# LN2_Autofill_Connectors.net
KiCad netlist of a schematic drawn in EAGLE
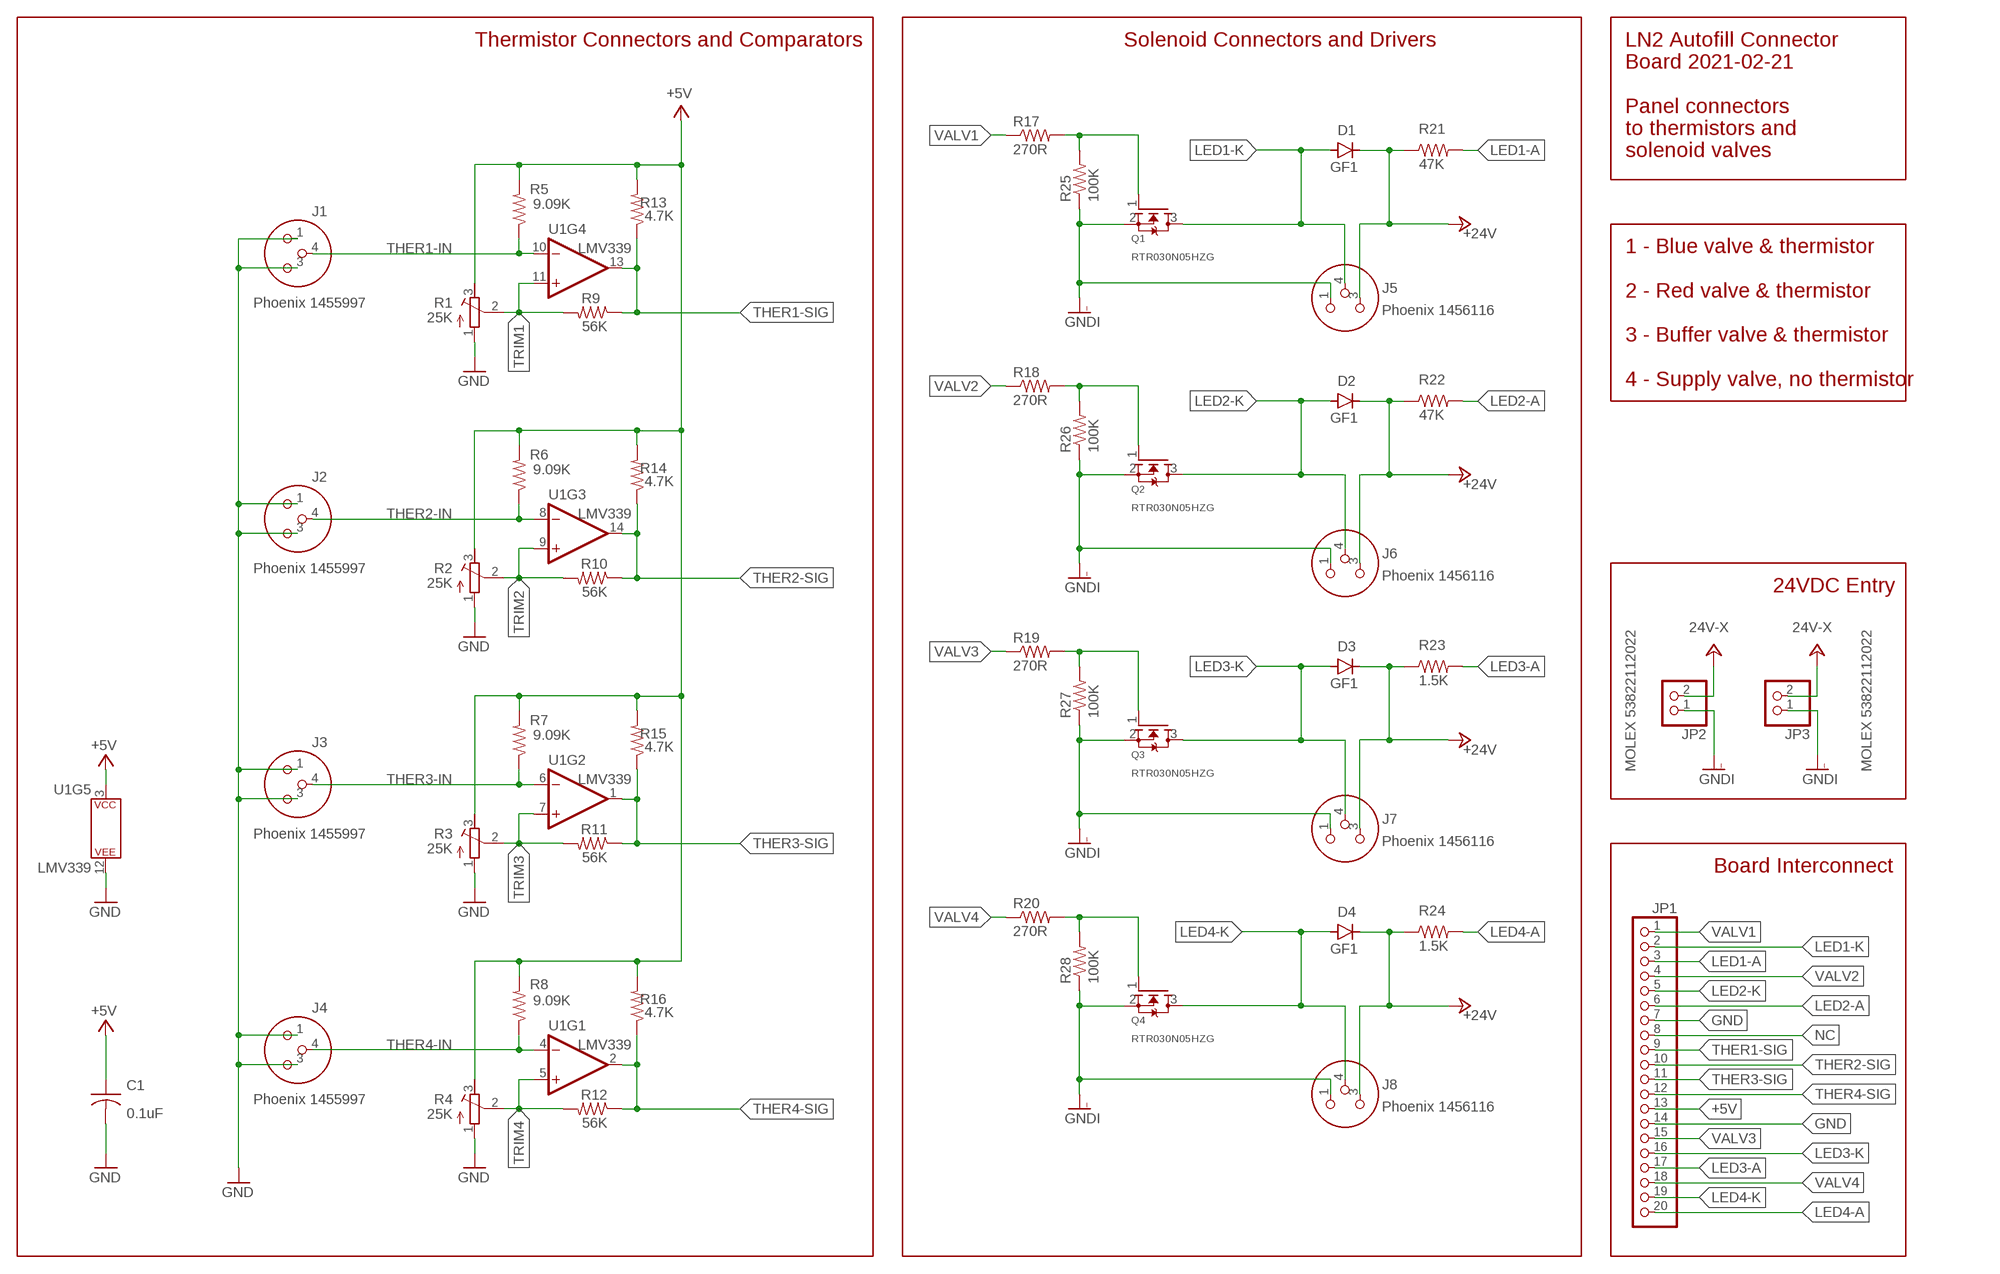
[diagram p0: schematic, sheet 1]

(export (version "E")
  (design (tool "Eeschema 10.0.6"))
  (components
    (comp (ref "C1")
      (value "0.1uF")
      (footprint "eagle-import:C0805")
      (libsource (lib "eagle-import") (part "C-USC0805"))
    )
    (comp (ref "D1")
      (value "GF1")
      (footprint "eagle-import:SMA-DO214AC")
      (libsource (lib "eagle-import") (part "GF1"))
    )
    (comp (ref "D2")
      (value "GF1")
      (footprint "eagle-import:SMA-DO214AC")
      (libsource (lib "eagle-import") (part "GF1"))
    )
    (comp (ref "D3")
      (value "GF1")
      (footprint "eagle-import:SMA-DO214AC")
      (libsource (lib "eagle-import") (part "GF1"))
    )
    (comp (ref "D4")
      (value "GF1")
      (footprint "eagle-import:SMA-DO214AC")
      (libsource (lib "eagle-import") (part "GF1"))
    )
    (comp (ref "J1")
      (value "Phoenix 1455997")
      (footprint "eagle-import:PHOENIX-3PIN")
      (libsource (lib "eagle-import") (part "PHOENIX-3PIN-MALE"))
    )
    (comp (ref "J2")
      (value "Phoenix 1455997")
      (footprint "eagle-import:PHOENIX-3PIN")
      (libsource (lib "eagle-import") (part "PHOENIX-3PIN-MALE"))
    )
    (comp (ref "J3")
      (value "Phoenix 1455997")
      (footprint "eagle-import:PHOENIX-3PIN")
      (libsource (lib "eagle-import") (part "PHOENIX-3PIN-MALE"))
    )
    (comp (ref "J4")
      (value "Phoenix 1455997")
      (footprint "eagle-import:PHOENIX-3PIN")
      (libsource (lib "eagle-import") (part "PHOENIX-3PIN-MALE"))
    )
    (comp (ref "J5")
      (value "Phoenix 1456116")
      (footprint "eagle-import:PHOENIX-3PIN-FEMALE")
      (libsource (lib "eagle-import") (part "PHOENIX-3PIN-FEMALE"))
    )
    (comp (ref "J6")
      (value "Phoenix 1456116")
      (footprint "eagle-import:PHOENIX-3PIN-FEMALE")
      (libsource (lib "eagle-import") (part "PHOENIX-3PIN-FEMALE"))
    )
    (comp (ref "J7")
      (value "Phoenix 1456116")
      (footprint "eagle-import:PHOENIX-3PIN-FEMALE")
      (libsource (lib "eagle-import") (part "PHOENIX-3PIN-FEMALE"))
    )
    (comp (ref "J8")
      (value "Phoenix 1456116")
      (footprint "eagle-import:PHOENIX-3PIN-FEMALE")
      (libsource (lib "eagle-import") (part "PHOENIX-3PIN-FEMALE"))
    )
    (comp (ref "JP1")
      (value "PINHD-1X20")
      (footprint "eagle-import:1X20")
      (libsource (lib "eagle-import") (part "PINHD-1X20"))
    )
    (comp (ref "JP2")
      (value "MOLEX 53822112022")
      (footprint "eagle-import:MOLEX-02-VERT")
      (libsource (lib "eagle-import") (part "PINHD-1X2MOLEX-02-VERT"))
    )
    (comp (ref "JP3")
      (value "MOLEX 53822112022")
      (footprint "eagle-import:MOLEX-02-VERT")
      (libsource (lib "eagle-import") (part "PINHD-1X2MOLEX-02-VERT"))
    )
    (comp (ref "Q1")
      (value "RTR030N05HZG")
      (footprint "eagle-import:SOT23")
      (libsource (lib "eagle-import") (part "MOSFET-NREFLOW"))
    )
    (comp (ref "Q2")
      (value "RTR030N05HZG")
      (footprint "eagle-import:SOT23")
      (libsource (lib "eagle-import") (part "MOSFET-NREFLOW"))
    )
    (comp (ref "Q3")
      (value "RTR030N05HZG")
      (footprint "eagle-import:SOT23")
      (libsource (lib "eagle-import") (part "MOSFET-NREFLOW"))
    )
    (comp (ref "Q4")
      (value "RTR030N05HZG")
      (footprint "eagle-import:SOT23")
      (libsource (lib "eagle-import") (part "MOSFET-NREFLOW"))
    )
    (comp (ref "R1")
      (value "25K")
      (footprint "eagle-import:RTRIM3296Y")
      (libsource (lib "eagle-import") (part "R-TRIMM3296Y"))
    )
    (comp (ref "R2")
      (value "25K")
      (footprint "eagle-import:RTRIM3296Y")
      (libsource (lib "eagle-import") (part "R-TRIMM3296Y"))
    )
    (comp (ref "R3")
      (value "25K")
      (footprint "eagle-import:RTRIM3296Y")
      (libsource (lib "eagle-import") (part "R-TRIMM3296Y"))
    )
    (comp (ref "R4")
      (value "25K")
      (footprint "eagle-import:RTRIM3296Y")
      (libsource (lib "eagle-import") (part "R-TRIMM3296Y"))
    )
    (comp (ref "R5")
      (value "9.09K")
      (footprint "eagle-import:R0805")
      (libsource (lib "eagle-import") (part "R-US_R0805"))
    )
    (comp (ref "R6")
      (value "9.09K")
      (footprint "eagle-import:R0805")
      (libsource (lib "eagle-import") (part "R-US_R0805"))
    )
    (comp (ref "R7")
      (value "9.09K")
      (footprint "eagle-import:R0805")
      (libsource (lib "eagle-import") (part "R-US_R0805"))
    )
    (comp (ref "R8")
      (value "9.09K")
      (footprint "eagle-import:R0805")
      (libsource (lib "eagle-import") (part "R-US_R0805"))
    )
    (comp (ref "R9")
      (value "56K")
      (footprint "eagle-import:R0805")
      (libsource (lib "eagle-import") (part "R-US_R0805"))
    )
    (comp (ref "R10")
      (value "56K")
      (footprint "eagle-import:R0805")
      (libsource (lib "eagle-import") (part "R-US_R0805"))
    )
    (comp (ref "R11")
      (value "56K")
      (footprint "eagle-import:R0805")
      (libsource (lib "eagle-import") (part "R-US_R0805"))
    )
    (comp (ref "R12")
      (value "56K")
      (footprint "eagle-import:R0805")
      (libsource (lib "eagle-import") (part "R-US_R0805"))
    )
    (comp (ref "R13")
      (value "4.7K")
      (footprint "eagle-import:R0805")
      (libsource (lib "eagle-import") (part "R-US_R0805"))
    )
    (comp (ref "R14")
      (value "4.7K")
      (footprint "eagle-import:R0805")
      (libsource (lib "eagle-import") (part "R-US_R0805"))
    )
    (comp (ref "R15")
      (value "4.7K")
      (footprint "eagle-import:R0805")
      (libsource (lib "eagle-import") (part "R-US_R0805"))
    )
    (comp (ref "R16")
      (value "4.7K")
      (footprint "eagle-import:R0805")
      (libsource (lib "eagle-import") (part "R-US_R0805"))
    )
    (comp (ref "R17")
      (value "270R")
      (footprint "eagle-import:R0805")
      (libsource (lib "eagle-import") (part "R-US_R0805"))
    )
    (comp (ref "R18")
      (value "270R")
      (footprint "eagle-import:R0805")
      (libsource (lib "eagle-import") (part "R-US_R0805"))
    )
    (comp (ref "R19")
      (value "270R")
      (footprint "eagle-import:R0805")
      (libsource (lib "eagle-import") (part "R-US_R0805"))
    )
    (comp (ref "R20")
      (value "270R")
      (footprint "eagle-import:R0805")
      (libsource (lib "eagle-import") (part "R-US_R0805"))
    )
    (comp (ref "R21")
      (value "47K")
      (footprint "eagle-import:R0805")
      (libsource (lib "eagle-import") (part "R-US_R0805"))
    )
    (comp (ref "R22")
      (value "47K")
      (footprint "eagle-import:R0805")
      (libsource (lib "eagle-import") (part "R-US_R0805"))
    )
    (comp (ref "R23")
      (value "1.5K")
      (footprint "eagle-import:R0805")
      (libsource (lib "eagle-import") (part "R-US_R0805"))
    )
    (comp (ref "R24")
      (value "1.5K")
      (footprint "eagle-import:R0805")
      (libsource (lib "eagle-import") (part "R-US_R0805"))
    )
    (comp (ref "R25")
      (value "100K")
      (footprint "eagle-import:R0805")
      (libsource (lib "eagle-import") (part "R-US_R0805"))
    )
    (comp (ref "R26")
      (value "100K")
      (footprint "eagle-import:R0805")
      (libsource (lib "eagle-import") (part "R-US_R0805"))
    )
    (comp (ref "R27")
      (value "100K")
      (footprint "eagle-import:R0805")
      (libsource (lib "eagle-import") (part "R-US_R0805"))
    )
    (comp (ref "R28")
      (value "100K")
      (footprint "eagle-import:R0805")
      (libsource (lib "eagle-import") (part "R-US_R0805"))
    )
    (comp (ref "U1")
      (value "LMV339")
      (footprint "eagle-import:SOIC127P599X175-14")
      (libsource (lib "eagle-import") (part "LM339SOIC-14"))
    )
  )
  (nets
    (net (code "1") (name "+5V") (class "Default")
      (node (ref "C1") (pin "1") (pinfunction "1_1") (pintype "passive"))
      (node (ref "JP1") (pin "13") (pinfunction "13_13") (pintype "passive"))
      (node (ref "R1") (pin "3") (pinfunction "E_3") (pintype "passive"))
      (node (ref "R13") (pin "2") (pinfunction "2_2") (pintype "passive"))
      (node (ref "R14") (pin "2") (pinfunction "2_2") (pintype "passive"))
      (node (ref "R15") (pin "2") (pinfunction "2_2") (pintype "passive"))
      (node (ref "R16") (pin "2") (pinfunction "2_2") (pintype "passive"))
      (node (ref "R2") (pin "3") (pinfunction "E_3") (pintype "passive"))
      (node (ref "R3") (pin "3") (pinfunction "E_3") (pintype "passive"))
      (node (ref "R4") (pin "3") (pinfunction "E_3") (pintype "passive"))
      (node (ref "R5") (pin "2") (pinfunction "2_2") (pintype "passive"))
      (node (ref "R6") (pin "2") (pinfunction "2_2") (pintype "passive"))
      (node (ref "R7") (pin "2") (pinfunction "2_2") (pintype "passive"))
      (node (ref "R8") (pin "2") (pinfunction "2_2") (pintype "passive"))
      (node (ref "U1") (pin "3") (pinfunction "P$V+_3") (pintype "bidirectional"))
    )
    (net (code "2") (name "+24V") (class "Default")
      (node (ref "D1") (pin "K") (pinfunction "C_K") (pintype "passive"))
      (node (ref "D2") (pin "K") (pinfunction "C_K") (pintype "passive"))
      (node (ref "D3") (pin "K") (pinfunction "C_K") (pintype "passive"))
      (node (ref "D4") (pin "K") (pinfunction "C_K") (pintype "passive"))
      (node (ref "J5") (pin "3") (pinfunction "3_3") (pintype "passive"))
      (node (ref "J6") (pin "3") (pinfunction "3_3") (pintype "passive"))
      (node (ref "J7") (pin "3") (pinfunction "3_3") (pintype "passive"))
      (node (ref "J8") (pin "3") (pinfunction "3_3") (pintype "passive"))
      (node (ref "JP2") (pin "2") (pinfunction "2_2") (pintype "passive"))
      (node (ref "JP3") (pin "2") (pinfunction "2_2") (pintype "passive"))
      (node (ref "R21") (pin "1") (pinfunction "1_1") (pintype "passive"))
      (node (ref "R22") (pin "1") (pinfunction "1_1") (pintype "passive"))
      (node (ref "R23") (pin "1") (pinfunction "1_1") (pintype "passive"))
      (node (ref "R24") (pin "1") (pinfunction "1_1") (pintype "passive"))
    )
    (net (code "3") (name "/THER1-IN") (class "Default")
      (node (ref "J1") (pin "4") (pinfunction "4_4") (pintype "passive"))
      (node (ref "R5") (pin "1") (pinfunction "1_1") (pintype "passive"))
      (node (ref "U1") (pin "10") (pinfunction "-IN_10") (pintype "input"))
    )
    (net (code "4") (name "/THER2-IN") (class "Default")
      (node (ref "J2") (pin "4") (pinfunction "4_4") (pintype "passive"))
      (node (ref "R6") (pin "1") (pinfunction "1_1") (pintype "passive"))
      (node (ref "U1") (pin "8") (pinfunction "-IN_8") (pintype "input"))
    )
    (net (code "5") (name "/THER3-IN") (class "Default")
      (node (ref "J3") (pin "4") (pinfunction "4_4") (pintype "passive"))
      (node (ref "R7") (pin "1") (pinfunction "1_1") (pintype "passive"))
      (node (ref "U1") (pin "6") (pinfunction "-IN_6") (pintype "input"))
    )
    (net (code "6") (name "/THER4-IN") (class "Default")
      (node (ref "J4") (pin "4") (pinfunction "4_4") (pintype "passive"))
      (node (ref "R8") (pin "1") (pinfunction "1_1") (pintype "passive"))
      (node (ref "U1") (pin "4") (pinfunction "-IN_4") (pintype "input"))
    )
    (net (code "7") (name "GND") (class "Default")
      (node (ref "C1") (pin "2") (pinfunction "2_2") (pintype "passive"))
      (node (ref "J1") (pin "1") (pinfunction "1_1") (pintype "passive"))
      (node (ref "J1") (pin "3") (pinfunction "3_3") (pintype "passive"))
      (node (ref "J2") (pin "1") (pinfunction "1_1") (pintype "passive"))
      (node (ref "J2") (pin "3") (pinfunction "3_3") (pintype "passive"))
      (node (ref "J3") (pin "1") (pinfunction "1_1") (pintype "passive"))
      (node (ref "J3") (pin "3") (pinfunction "3_3") (pintype "passive"))
      (node (ref "J4") (pin "1") (pinfunction "1_1") (pintype "passive"))
      (node (ref "J4") (pin "3") (pinfunction "3_3") (pintype "passive"))
      (node (ref "JP1") (pin "14") (pinfunction "14_14") (pintype "passive"))
      (node (ref "JP1") (pin "7") (pinfunction "7_7") (pintype "passive"))
      (node (ref "R1") (pin "1") (pinfunction "A_1") (pintype "passive"))
      (node (ref "R2") (pin "1") (pinfunction "A_1") (pintype "passive"))
      (node (ref "R3") (pin "1") (pinfunction "A_1") (pintype "passive"))
      (node (ref "R4") (pin "1") (pinfunction "A_1") (pintype "passive"))
      (node (ref "U1") (pin "12") (pinfunction "P$V-_12") (pintype "bidirectional"))
    )
    (net (code "8") (name "GNDI") (class "Default")
      (node (ref "J5") (pin "1") (pinfunction "1_1") (pintype "passive"))
      (node (ref "J6") (pin "1") (pinfunction "1_1") (pintype "passive"))
      (node (ref "J7") (pin "1") (pinfunction "1_1") (pintype "passive"))
      (node (ref "J8") (pin "1") (pinfunction "1_1") (pintype "passive"))
      (node (ref "JP2") (pin "1") (pinfunction "1_1") (pintype "passive"))
      (node (ref "JP3") (pin "1") (pinfunction "1_1") (pintype "passive"))
      (node (ref "Q1") (pin "2") (pinfunction "S_2") (pintype "bidirectional"))
      (node (ref "Q2") (pin "2") (pinfunction "S_2") (pintype "bidirectional"))
      (node (ref "Q3") (pin "2") (pinfunction "S_2") (pintype "bidirectional"))
      (node (ref "Q4") (pin "2") (pinfunction "S_2") (pintype "bidirectional"))
      (node (ref "R25") (pin "1") (pinfunction "1_1") (pintype "passive"))
      (node (ref "R26") (pin "1") (pinfunction "1_1") (pintype "passive"))
      (node (ref "R27") (pin "1") (pinfunction "1_1") (pintype "passive"))
      (node (ref "R28") (pin "1") (pinfunction "1_1") (pintype "passive"))
    )
    (net (code "9") (name "LED1-A") (class "Default")
      (node (ref "JP1") (pin "3") (pinfunction "3_3") (pintype "passive"))
      (node (ref "R21") (pin "2") (pinfunction "2_2") (pintype "passive"))
    )
    (net (code "10") (name "LED1-K") (class "Default")
      (node (ref "D1") (pin "A") (pinfunction "A_A") (pintype "passive"))
      (node (ref "J5") (pin "4") (pinfunction "4_4") (pintype "passive"))
      (node (ref "JP1") (pin "2") (pinfunction "2_2") (pintype "passive"))
      (node (ref "Q1") (pin "3") (pinfunction "D_3") (pintype "bidirectional"))
    )
    (net (code "11") (name "LED2-A") (class "Default")
      (node (ref "JP1") (pin "6") (pinfunction "6_6") (pintype "passive"))
      (node (ref "R22") (pin "2") (pinfunction "2_2") (pintype "passive"))
    )
    (net (code "12") (name "LED2-K") (class "Default")
      (node (ref "D2") (pin "A") (pinfunction "A_A") (pintype "passive"))
      (node (ref "J6") (pin "4") (pinfunction "4_4") (pintype "passive"))
      (node (ref "JP1") (pin "5") (pinfunction "5_5") (pintype "passive"))
      (node (ref "Q2") (pin "3") (pinfunction "D_3") (pintype "bidirectional"))
    )
    (net (code "13") (name "LED3-A") (class "Default")
      (node (ref "JP1") (pin "17") (pinfunction "17_17") (pintype "passive"))
      (node (ref "R23") (pin "2") (pinfunction "2_2") (pintype "passive"))
    )
    (net (code "14") (name "LED3-K") (class "Default")
      (node (ref "D3") (pin "A") (pinfunction "A_A") (pintype "passive"))
      (node (ref "J7") (pin "4") (pinfunction "4_4") (pintype "passive"))
      (node (ref "JP1") (pin "16") (pinfunction "16_16") (pintype "passive"))
      (node (ref "Q3") (pin "3") (pinfunction "D_3") (pintype "bidirectional"))
    )
    (net (code "15") (name "LED4-A") (class "Default")
      (node (ref "JP1") (pin "20") (pinfunction "20_20") (pintype "passive"))
      (node (ref "R24") (pin "2") (pinfunction "2_2") (pintype "passive"))
    )
    (net (code "16") (name "LED4-K") (class "Default")
      (node (ref "D4") (pin "A") (pinfunction "A_A") (pintype "passive"))
      (node (ref "J8") (pin "4") (pinfunction "4_4") (pintype "passive"))
      (node (ref "JP1") (pin "19") (pinfunction "19_19") (pintype "passive"))
      (node (ref "Q4") (pin "3") (pinfunction "D_3") (pintype "bidirectional"))
    )
    (net (code "17") (name "NC") (class "Default")
      (node (ref "JP1") (pin "8") (pinfunction "8_8") (pintype "passive"))
    )
    (net (code "18") (name "Net-(Q1-G)") (class "Default")
      (node (ref "Q1") (pin "1") (pinfunction "G_1") (pintype "bidirectional"))
      (node (ref "R17") (pin "2") (pinfunction "2_2") (pintype "passive"))
      (node (ref "R25") (pin "2") (pinfunction "2_2") (pintype "passive"))
    )
    (net (code "19") (name "Net-(Q2-G)") (class "Default")
      (node (ref "Q2") (pin "1") (pinfunction "G_1") (pintype "bidirectional"))
      (node (ref "R18") (pin "2") (pinfunction "2_2") (pintype "passive"))
      (node (ref "R26") (pin "2") (pinfunction "2_2") (pintype "passive"))
    )
    (net (code "20") (name "Net-(Q3-G)") (class "Default")
      (node (ref "Q3") (pin "1") (pinfunction "G_1") (pintype "bidirectional"))
      (node (ref "R19") (pin "2") (pinfunction "2_2") (pintype "passive"))
      (node (ref "R27") (pin "2") (pinfunction "2_2") (pintype "passive"))
    )
    (net (code "21") (name "Net-(Q4-G)") (class "Default")
      (node (ref "Q4") (pin "1") (pinfunction "G_1") (pintype "bidirectional"))
      (node (ref "R20") (pin "2") (pinfunction "2_2") (pintype "passive"))
      (node (ref "R28") (pin "2") (pinfunction "2_2") (pintype "passive"))
    )
    (net (code "22") (name "THER1-SIG") (class "Default")
      (node (ref "JP1") (pin "9") (pinfunction "9_9") (pintype "passive"))
      (node (ref "R13") (pin "1") (pinfunction "1_1") (pintype "passive"))
      (node (ref "R9") (pin "1") (pinfunction "1_1") (pintype "passive"))
      (node (ref "U1") (pin "13") (pinfunction "OUT_13") (pintype "output"))
    )
    (net (code "23") (name "THER2-SIG") (class "Default")
      (node (ref "JP1") (pin "10") (pinfunction "10_10") (pintype "passive"))
      (node (ref "R10") (pin "1") (pinfunction "1_1") (pintype "passive"))
      (node (ref "R14") (pin "1") (pinfunction "1_1") (pintype "passive"))
      (node (ref "U1") (pin "14") (pinfunction "OUT_14") (pintype "output"))
    )
    (net (code "24") (name "THER3-SIG") (class "Default")
      (node (ref "JP1") (pin "11") (pinfunction "11_11") (pintype "passive"))
      (node (ref "R11") (pin "1") (pinfunction "1_1") (pintype "passive"))
      (node (ref "R15") (pin "1") (pinfunction "1_1") (pintype "passive"))
      (node (ref "U1") (pin "1") (pinfunction "OUT_1") (pintype "output"))
    )
    (net (code "25") (name "THER4-SIG") (class "Default")
      (node (ref "JP1") (pin "12") (pinfunction "12_12") (pintype "passive"))
      (node (ref "R12") (pin "1") (pinfunction "1_1") (pintype "passive"))
      (node (ref "R16") (pin "1") (pinfunction "1_1") (pintype "passive"))
      (node (ref "U1") (pin "2") (pinfunction "OUT_2") (pintype "output"))
    )
    (net (code "26") (name "TRIM1") (class "Default")
      (node (ref "R1") (pin "2") (pinfunction "S_2") (pintype "passive"))
      (node (ref "R9") (pin "2") (pinfunction "2_2") (pintype "passive"))
      (node (ref "U1") (pin "11") (pinfunction "+IN_11") (pintype "input"))
    )
    (net (code "27") (name "TRIM2") (class "Default")
      (node (ref "R10") (pin "2") (pinfunction "2_2") (pintype "passive"))
      (node (ref "R2") (pin "2") (pinfunction "S_2") (pintype "passive"))
      (node (ref "U1") (pin "9") (pinfunction "+IN_9") (pintype "input"))
    )
    (net (code "28") (name "TRIM3") (class "Default")
      (node (ref "R11") (pin "2") (pinfunction "2_2") (pintype "passive"))
      (node (ref "R3") (pin "2") (pinfunction "S_2") (pintype "passive"))
      (node (ref "U1") (pin "7") (pinfunction "+IN_7") (pintype "input"))
    )
    (net (code "29") (name "TRIM4") (class "Default")
      (node (ref "R12") (pin "2") (pinfunction "2_2") (pintype "passive"))
      (node (ref "R4") (pin "2") (pinfunction "S_2") (pintype "passive"))
      (node (ref "U1") (pin "5") (pinfunction "+IN_5") (pintype "input"))
    )
    (net (code "30") (name "VALV1") (class "Default")
      (node (ref "JP1") (pin "1") (pinfunction "1_1") (pintype "passive"))
      (node (ref "R17") (pin "1") (pinfunction "1_1") (pintype "passive"))
    )
    (net (code "31") (name "VALV2") (class "Default")
      (node (ref "JP1") (pin "4") (pinfunction "4_4") (pintype "passive"))
      (node (ref "R18") (pin "1") (pinfunction "1_1") (pintype "passive"))
    )
    (net (code "32") (name "VALV3") (class "Default")
      (node (ref "JP1") (pin "15") (pinfunction "15_15") (pintype "passive"))
      (node (ref "R19") (pin "1") (pinfunction "1_1") (pintype "passive"))
    )
    (net (code "33") (name "VALV4") (class "Default")
      (node (ref "JP1") (pin "18") (pinfunction "18_18") (pintype "passive"))
      (node (ref "R20") (pin "1") (pinfunction "1_1") (pintype "passive"))
    )
  )
)
